# demo.net
KiCad netlist of a schematic drawn in EAGLE
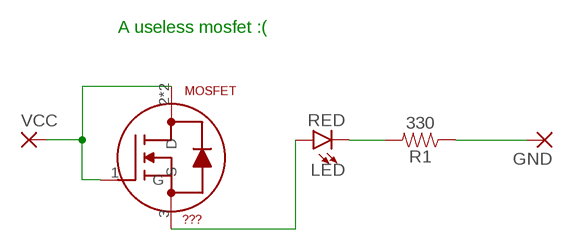
[diagram p0: schematic, sheet 1]

(export (version "E")
  (design (tool "Eeschema 10.0.6"))
  (components
    (comp (ref "GND")
      (value "SMD2")
      (footprint "eagle-import:SMD1,27-2,54")
      (libsource (lib "eagle-import") (part "SMD2"))
    )
    (comp (ref "LED")
      (value "RED")
      (footprint "eagle-import:LED-1206")
      (libsource (lib "eagle-import") (part "LED-RED1206"))
    )
    (comp (ref "MOSFET")
      (value "???")
      (footprint "eagle-import:CSTM_MOSFET")
      (libsource (lib "eagle-import") (part "CSTM_MOSFET"))
    )
    (comp (ref "R1")
      (value "330")
      (footprint "eagle-import:1206")
      (libsource (lib "eagle-import") (part "RESISTOR1206"))
    )
    (comp (ref "VCC")
      (value "SMD2")
      (footprint "eagle-import:SMD1,27-2,54")
      (libsource (lib "eagle-import") (part "SMD2"))
    )
  )
  (nets
    (net (code "1") (name "Net-(GND-P)") (class "Default")
      (node (ref "GND") (pin "1") (pinfunction "P_1") (pintype "passive"))
      (node (ref "R1") (pin "1") (pinfunction "1_1") (pintype "passive"))
    )
    (net (code "2") (name "Net-(LED-PadC)") (class "Default")
      (node (ref "LED") (pin "C") (pinfunction "C_C") (pintype "passive"))
      (node (ref "R1") (pin "2") (pinfunction "2_2") (pintype "passive"))
    )
    (net (code "3") (name "Net-(MOSFET-G)") (class "Default")
      (node (ref "MOSFET") (pin "1") (pinfunction "G_1") (pintype "bidirectional"))
      (node (ref "MOSFET") (pin "2") (pinfunction "D_2") (pintype "bidirectional"))
      (node (ref "MOSFET") (pin "2B") (pinfunction "D_2B") (pintype "bidirectional"))
      (node (ref "VCC") (pin "1") (pinfunction "P_1") (pintype "passive"))
    )
    (net (code "4") (name "Net-(MOSFET-S)") (class "Default")
      (node (ref "LED") (pin "A") (pinfunction "A_A") (pintype "passive"))
      (node (ref "MOSFET") (pin "3") (pinfunction "S_3") (pintype "bidirectional"))
    )
  )
)
